# TILaunchpad.net
KiCad netlist of a schematic drawn in Altium Designer
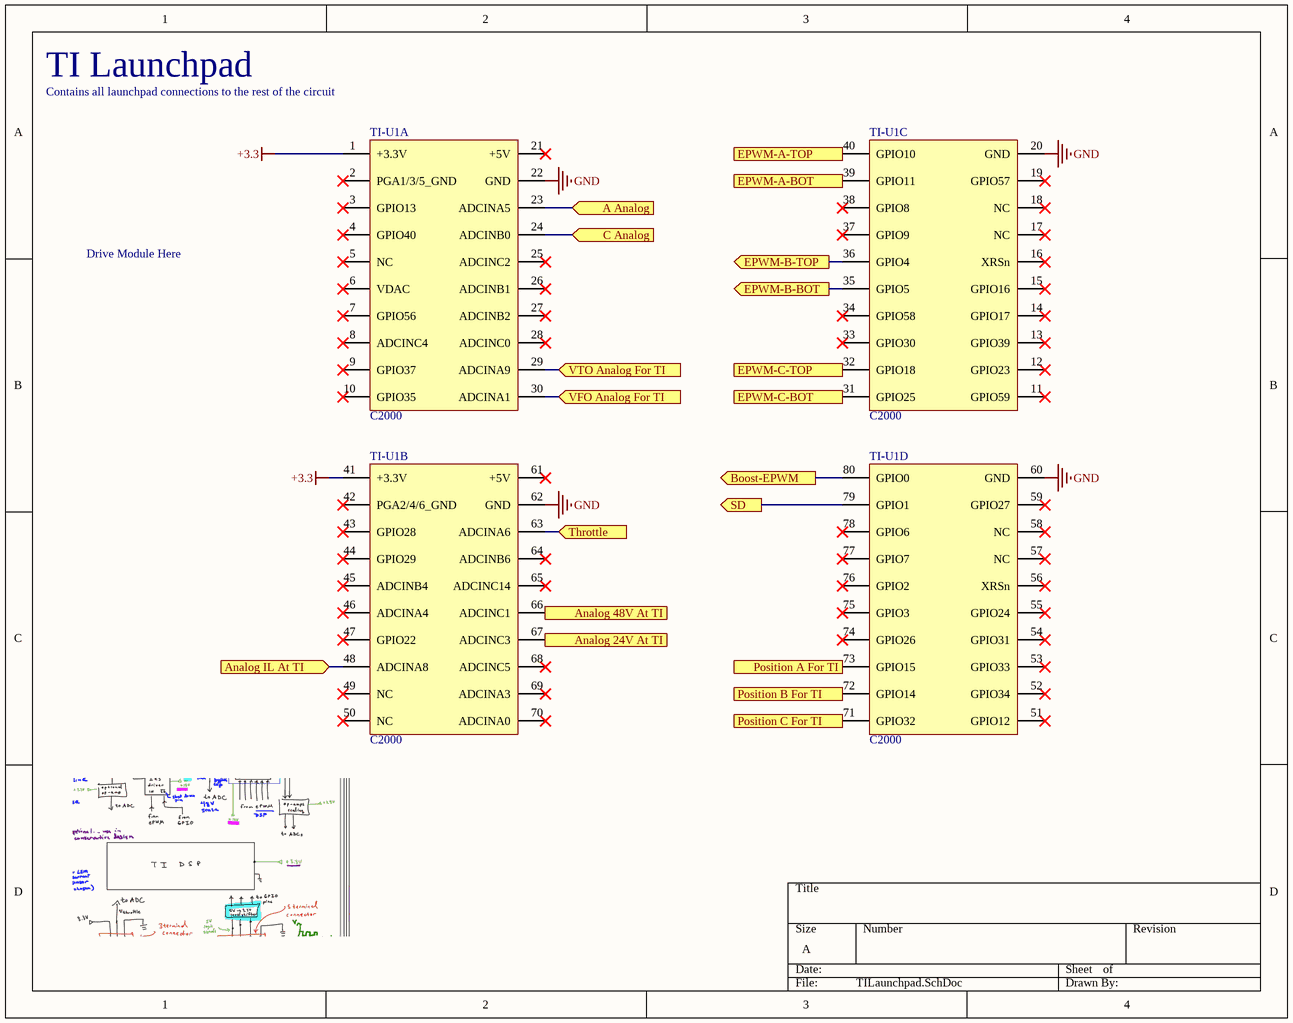
[diagram p0: TILaunchpad.SchDoc]

(export (version "E")
  (design (tool "Eeschema 10.0.6"))
  (components
    (comp (ref "TI-U1")
      (value "C2000")
      (footprint "C2000")
      (description "F280049C")
      (libsource (lib "ee_453_yourname") (part "C2000"))
    )
  )
  (nets
    (net (code "1") (name "+3.3") (class "Default")
      (node (ref "TI-U1") (pin "1") (pinfunction "+3.3V_1") (pintype "passive"))
      (node (ref "TI-U1") (pin "41") (pinfunction "+3.3V_41") (pintype "passive"))
    )
    (net (code "2") (name "/A Analog") (class "Default")
      (node (ref "TI-U1") (pin "23") (pinfunction "ADCINA5_23") (pintype "passive"))
    )
    (net (code "3") (name "/Analog 24V At TI") (class "Default")
      (node (ref "TI-U1") (pin "67") (pinfunction "ADCINC3_67") (pintype "passive"))
    )
    (net (code "4") (name "/Analog 48V At TI") (class "Default")
      (node (ref "TI-U1") (pin "66") (pinfunction "ADCINC1_66") (pintype "passive"))
    )
    (net (code "5") (name "/Analog IL At TI") (class "Default")
      (node (ref "TI-U1") (pin "48") (pinfunction "ADCINA8_48") (pintype "passive"))
    )
    (net (code "6") (name "/Boost-EPWM") (class "Default")
      (node (ref "TI-U1") (pin "80") (pinfunction "GPIO0_80") (pintype "passive"))
    )
    (net (code "7") (name "/C Analog") (class "Default")
      (node (ref "TI-U1") (pin "24") (pinfunction "ADCINB0_24") (pintype "passive"))
    )
    (net (code "8") (name "/EPWM-A-BOT") (class "Default")
      (node (ref "TI-U1") (pin "39") (pinfunction "GPIO11_39") (pintype "passive"))
    )
    (net (code "9") (name "/EPWM-A-TOP") (class "Default")
      (node (ref "TI-U1") (pin "40") (pinfunction "GPIO10_40") (pintype "passive"))
    )
    (net (code "10") (name "/EPWM-B-BOT") (class "Default")
      (node (ref "TI-U1") (pin "35") (pinfunction "GPIO5_35") (pintype "passive"))
    )
    (net (code "11") (name "/EPWM-B-TOP") (class "Default")
      (node (ref "TI-U1") (pin "36") (pinfunction "GPIO4_36") (pintype "passive"))
    )
    (net (code "12") (name "/EPWM-C-BOT") (class "Default")
      (node (ref "TI-U1") (pin "31") (pinfunction "GPIO25_31") (pintype "passive"))
    )
    (net (code "13") (name "/EPWM-C-TOP") (class "Default")
      (node (ref "TI-U1") (pin "32") (pinfunction "GPIO18_32") (pintype "passive"))
    )
    (net (code "14") (name "/Position A For TI") (class "Default")
      (node (ref "TI-U1") (pin "73") (pinfunction "GPIO15_73") (pintype "passive"))
    )
    (net (code "15") (name "/Position B For TI") (class "Default")
      (node (ref "TI-U1") (pin "72") (pinfunction "GPIO14_72") (pintype "passive"))
    )
    (net (code "16") (name "/Position C For TI") (class "Default")
      (node (ref "TI-U1") (pin "71") (pinfunction "GPIO32_71") (pintype "passive"))
    )
    (net (code "17") (name "/SD") (class "Default")
      (node (ref "TI-U1") (pin "79") (pinfunction "GPIO1_79") (pintype "passive"))
    )
    (net (code "18") (name "/Throttle") (class "Default")
      (node (ref "TI-U1") (pin "63") (pinfunction "ADCINA6_63") (pintype "passive"))
    )
    (net (code "19") (name "/VFO Analog For TI") (class "Default")
      (node (ref "TI-U1") (pin "30") (pinfunction "ADCINA1_30") (pintype "passive"))
    )
    (net (code "20") (name "/VTO Analog For TI") (class "Default")
      (node (ref "TI-U1") (pin "29") (pinfunction "ADCINA9_29") (pintype "passive"))
    )
    (net (code "21") (name "GND") (class "Default")
      (node (ref "TI-U1") (pin "20") (pinfunction "GND_20") (pintype "passive"))
      (node (ref "TI-U1") (pin "22") (pinfunction "GND_22") (pintype "passive"))
      (node (ref "TI-U1") (pin "60") (pinfunction "GND_60") (pintype "passive"))
      (node (ref "TI-U1") (pin "62") (pinfunction "GND_62") (pintype "passive"))
    )
    (net (code "22") (name "unconnected-(TI-U1A-+5V-Pad21)") (class "Default")
      (node (ref "TI-U1") (pin "21") (pinfunction "+5V_21") (pintype "passive+no_connect"))
    )
    (net (code "23") (name "unconnected-(TI-U1A-ADCINB1-Pad26)") (class "Default")
      (node (ref "TI-U1") (pin "26") (pinfunction "ADCINB1_26") (pintype "passive+no_connect"))
    )
    (net (code "24") (name "unconnected-(TI-U1A-ADCINB2-Pad27)") (class "Default")
      (node (ref "TI-U1") (pin "27") (pinfunction "ADCINB2_27") (pintype "passive+no_connect"))
    )
    (net (code "25") (name "unconnected-(TI-U1A-ADCINC0-Pad28)") (class "Default")
      (node (ref "TI-U1") (pin "28") (pinfunction "ADCINC0_28") (pintype "passive+no_connect"))
    )
    (net (code "26") (name "unconnected-(TI-U1A-ADCINC2-Pad25)") (class "Default")
      (node (ref "TI-U1") (pin "25") (pinfunction "ADCINC2_25") (pintype "passive+no_connect"))
    )
    (net (code "27") (name "unconnected-(TI-U1A-ADCINC4-Pad8)") (class "Default")
      (node (ref "TI-U1") (pin "8") (pinfunction "ADCINC4_8") (pintype "passive+no_connect"))
    )
    (net (code "28") (name "unconnected-(TI-U1A-GPIO13-Pad3)") (class "Default")
      (node (ref "TI-U1") (pin "3") (pinfunction "GPIO13_3") (pintype "passive+no_connect"))
    )
    (net (code "29") (name "unconnected-(TI-U1A-GPIO35-Pad10)") (class "Default")
      (node (ref "TI-U1") (pin "10") (pinfunction "GPIO35_10") (pintype "passive+no_connect"))
    )
    (net (code "30") (name "unconnected-(TI-U1A-GPIO37-Pad9)") (class "Default")
      (node (ref "TI-U1") (pin "9") (pinfunction "GPIO37_9") (pintype "passive+no_connect"))
    )
    (net (code "31") (name "unconnected-(TI-U1A-GPIO40-Pad4)") (class "Default")
      (node (ref "TI-U1") (pin "4") (pinfunction "GPIO40_4") (pintype "passive+no_connect"))
    )
    (net (code "32") (name "unconnected-(TI-U1A-GPIO56-Pad7)") (class "Default")
      (node (ref "TI-U1") (pin "7") (pinfunction "GPIO56_7") (pintype "passive+no_connect"))
    )
    (net (code "33") (name "unconnected-(TI-U1A-NC-Pad5)") (class "Default")
      (node (ref "TI-U1") (pin "5") (pinfunction "NC_5") (pintype "passive+no_connect"))
    )
    (net (code "34") (name "unconnected-(TI-U1A-PGA1{slash}3{slash}5_GND-Pad2)") (class "Default")
      (node (ref "TI-U1") (pin "2") (pinfunction "PGA1/3/5_GND_2") (pintype "passive+no_connect"))
    )
    (net (code "35") (name "unconnected-(TI-U1A-VDAC-Pad6)") (class "Default")
      (node (ref "TI-U1") (pin "6") (pinfunction "VDAC_6") (pintype "passive+no_connect"))
    )
    (net (code "36") (name "unconnected-(TI-U1B-+5V-Pad61)") (class "Default")
      (node (ref "TI-U1") (pin "61") (pinfunction "+5V_61") (pintype "passive+no_connect"))
    )
    (net (code "37") (name "unconnected-(TI-U1B-ADCINA0-Pad70)") (class "Default")
      (node (ref "TI-U1") (pin "70") (pinfunction "ADCINA0_70") (pintype "passive+no_connect"))
    )
    (net (code "38") (name "unconnected-(TI-U1B-ADCINA3-Pad69)") (class "Default")
      (node (ref "TI-U1") (pin "69") (pinfunction "ADCINA3_69") (pintype "passive+no_connect"))
    )
    (net (code "39") (name "unconnected-(TI-U1B-ADCINA4-Pad46)") (class "Default")
      (node (ref "TI-U1") (pin "46") (pinfunction "ADCINA4_46") (pintype "passive+no_connect"))
    )
    (net (code "40") (name "unconnected-(TI-U1B-ADCINB4-Pad45)") (class "Default")
      (node (ref "TI-U1") (pin "45") (pinfunction "ADCINB4_45") (pintype "passive+no_connect"))
    )
    (net (code "41") (name "unconnected-(TI-U1B-ADCINB6-Pad64)") (class "Default")
      (node (ref "TI-U1") (pin "64") (pinfunction "ADCINB6_64") (pintype "passive+no_connect"))
    )
    (net (code "42") (name "unconnected-(TI-U1B-ADCINC5-Pad68)") (class "Default")
      (node (ref "TI-U1") (pin "68") (pinfunction "ADCINC5_68") (pintype "passive+no_connect"))
    )
    (net (code "43") (name "unconnected-(TI-U1B-ADCINC14-Pad65)") (class "Default")
      (node (ref "TI-U1") (pin "65") (pinfunction "ADCINC14_65") (pintype "passive+no_connect"))
    )
    (net (code "44") (name "unconnected-(TI-U1B-GPIO22-Pad47)") (class "Default")
      (node (ref "TI-U1") (pin "47") (pinfunction "GPIO22_47") (pintype "passive+no_connect"))
    )
    (net (code "45") (name "unconnected-(TI-U1B-GPIO28-Pad43)") (class "Default")
      (node (ref "TI-U1") (pin "43") (pinfunction "GPIO28_43") (pintype "passive+no_connect"))
    )
    (net (code "46") (name "unconnected-(TI-U1B-GPIO29-Pad44)") (class "Default")
      (node (ref "TI-U1") (pin "44") (pinfunction "GPIO29_44") (pintype "passive+no_connect"))
    )
    (net (code "47") (name "unconnected-(TI-U1B-NC-Pad49)") (class "Default")
      (node (ref "TI-U1") (pin "49") (pinfunction "NC_49") (pintype "passive+no_connect"))
    )
    (net (code "48") (name "unconnected-(TI-U1B-NC-Pad50)") (class "Default")
      (node (ref "TI-U1") (pin "50") (pinfunction "NC_50") (pintype "passive+no_connect"))
    )
    (net (code "49") (name "unconnected-(TI-U1B-PGA2{slash}4{slash}6_GND-Pad42)") (class "Default")
      (node (ref "TI-U1") (pin "42") (pinfunction "PGA2/4/6_GND_42") (pintype "passive+no_connect"))
    )
    (net (code "50") (name "unconnected-(TI-U1C-GPIO8-Pad38)") (class "Default")
      (node (ref "TI-U1") (pin "38") (pinfunction "GPIO8_38") (pintype "passive+no_connect"))
    )
    (net (code "51") (name "unconnected-(TI-U1C-GPIO9-Pad37)") (class "Default")
      (node (ref "TI-U1") (pin "37") (pinfunction "GPIO9_37") (pintype "passive+no_connect"))
    )
    (net (code "52") (name "unconnected-(TI-U1C-GPIO16-Pad15)") (class "Default")
      (node (ref "TI-U1") (pin "15") (pinfunction "GPIO16_15") (pintype "passive+no_connect"))
    )
    (net (code "53") (name "unconnected-(TI-U1C-GPIO17-Pad14)") (class "Default")
      (node (ref "TI-U1") (pin "14") (pinfunction "GPIO17_14") (pintype "passive+no_connect"))
    )
    (net (code "54") (name "unconnected-(TI-U1C-GPIO23-Pad12)") (class "Default")
      (node (ref "TI-U1") (pin "12") (pinfunction "GPIO23_12") (pintype "passive+no_connect"))
    )
    (net (code "55") (name "unconnected-(TI-U1C-GPIO30-Pad33)") (class "Default")
      (node (ref "TI-U1") (pin "33") (pinfunction "GPIO30_33") (pintype "passive+no_connect"))
    )
    (net (code "56") (name "unconnected-(TI-U1C-GPIO39-Pad13)") (class "Default")
      (node (ref "TI-U1") (pin "13") (pinfunction "GPIO39_13") (pintype "passive+no_connect"))
    )
    (net (code "57") (name "unconnected-(TI-U1C-GPIO57-Pad19)") (class "Default")
      (node (ref "TI-U1") (pin "19") (pinfunction "GPIO57_19") (pintype "passive+no_connect"))
    )
    (net (code "58") (name "unconnected-(TI-U1C-GPIO58-Pad34)") (class "Default")
      (node (ref "TI-U1") (pin "34") (pinfunction "GPIO58_34") (pintype "passive+no_connect"))
    )
    (net (code "59") (name "unconnected-(TI-U1C-GPIO59-Pad11)") (class "Default")
      (node (ref "TI-U1") (pin "11") (pinfunction "GPIO59_11") (pintype "passive+no_connect"))
    )
    (net (code "60") (name "unconnected-(TI-U1C-NC-Pad17)") (class "Default")
      (node (ref "TI-U1") (pin "17") (pinfunction "NC_17") (pintype "passive+no_connect"))
    )
    (net (code "61") (name "unconnected-(TI-U1C-NC-Pad18)") (class "Default")
      (node (ref "TI-U1") (pin "18") (pinfunction "NC_18") (pintype "passive+no_connect"))
    )
    (net (code "62") (name "unconnected-(TI-U1C-XRSn-Pad16)") (class "Default")
      (node (ref "TI-U1") (pin "16") (pinfunction "XRSn_16") (pintype "passive+no_connect"))
    )
    (net (code "63") (name "unconnected-(TI-U1D-GPIO2-Pad76)") (class "Default")
      (node (ref "TI-U1") (pin "76") (pinfunction "GPIO2_76") (pintype "passive+no_connect"))
    )
    (net (code "64") (name "unconnected-(TI-U1D-GPIO3-Pad75)") (class "Default")
      (node (ref "TI-U1") (pin "75") (pinfunction "GPIO3_75") (pintype "passive+no_connect"))
    )
    (net (code "65") (name "unconnected-(TI-U1D-GPIO6-Pad78)") (class "Default")
      (node (ref "TI-U1") (pin "78") (pinfunction "GPIO6_78") (pintype "passive+no_connect"))
    )
    (net (code "66") (name "unconnected-(TI-U1D-GPIO7-Pad77)") (class "Default")
      (node (ref "TI-U1") (pin "77") (pinfunction "GPIO7_77") (pintype "passive+no_connect"))
    )
    (net (code "67") (name "unconnected-(TI-U1D-GPIO12-Pad51)") (class "Default")
      (node (ref "TI-U1") (pin "51") (pinfunction "GPIO12_51") (pintype "passive+no_connect"))
    )
    (net (code "68") (name "unconnected-(TI-U1D-GPIO24-Pad55)") (class "Default")
      (node (ref "TI-U1") (pin "55") (pinfunction "GPIO24_55") (pintype "passive+no_connect"))
    )
    (net (code "69") (name "unconnected-(TI-U1D-GPIO26-Pad74)") (class "Default")
      (node (ref "TI-U1") (pin "74") (pinfunction "GPIO26_74") (pintype "passive+no_connect"))
    )
    (net (code "70") (name "unconnected-(TI-U1D-GPIO27-Pad59)") (class "Default")
      (node (ref "TI-U1") (pin "59") (pinfunction "GPIO27_59") (pintype "passive+no_connect"))
    )
    (net (code "71") (name "unconnected-(TI-U1D-GPIO31-Pad54)") (class "Default")
      (node (ref "TI-U1") (pin "54") (pinfunction "GPIO31_54") (pintype "passive+no_connect"))
    )
    (net (code "72") (name "unconnected-(TI-U1D-GPIO33-Pad53)") (class "Default")
      (node (ref "TI-U1") (pin "53") (pinfunction "GPIO33_53") (pintype "passive+no_connect"))
    )
    (net (code "73") (name "unconnected-(TI-U1D-GPIO34-Pad52)") (class "Default")
      (node (ref "TI-U1") (pin "52") (pinfunction "GPIO34_52") (pintype "passive+no_connect"))
    )
    (net (code "74") (name "unconnected-(TI-U1D-NC-Pad57)") (class "Default")
      (node (ref "TI-U1") (pin "57") (pinfunction "NC_57") (pintype "passive+no_connect"))
    )
    (net (code "75") (name "unconnected-(TI-U1D-NC-Pad58)") (class "Default")
      (node (ref "TI-U1") (pin "58") (pinfunction "NC_58") (pintype "passive+no_connect"))
    )
    (net (code "76") (name "unconnected-(TI-U1D-XRSn-Pad56)") (class "Default")
      (node (ref "TI-U1") (pin "56") (pinfunction "XRSn_56") (pintype "passive+no_connect"))
    )
  )
)
